# TLV75533PDRVR.net
KiCad netlist of a schematic drawn in Altium Designer
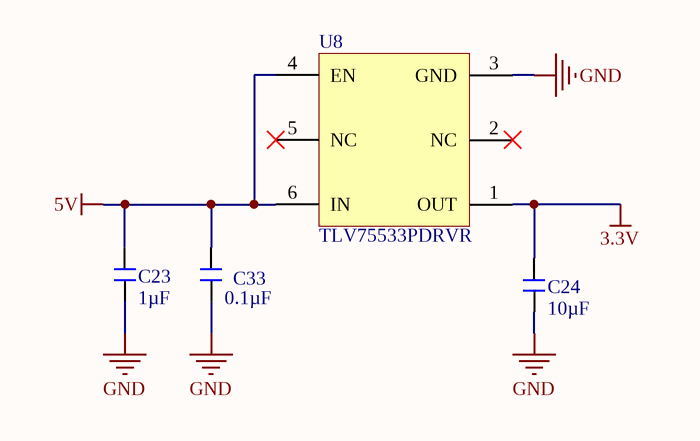
[diagram p0: TLV75533PDRVR.SchDoc]

(export (version "E")
  (design (tool "Eeschema 10.0.6"))
  (components
    (comp (ref "C23")
      (value "1µF")
      (footprint "402 capacitor - duplicate")
      (description "CAP SMD 402")
      (fields (field (name "MPN") "GRM155R6YA105KE11D") (field (name "Comment") "0402 capacitor"))
      (libsource (lib "Schlib1") (part "CAP SMD 402"))
    )
    (comp (ref "C24")
      (value "10µF")
      (footprint "603 CAPACITOR")
      (description "CON SMD 0603")
      (fields (field (name "MPN") "GRM188R61E106MA73D") (field (name "Comment") "0603 CAPACİTOR"))
      (libsource (lib "Schlib1") (part "CON SMD 0603"))
    )
    (comp (ref "C33")
      (value "0.1µF")
      (footprint "402 capacitor - duplicate")
      (description "CAP SMD 402")
      (fields (field (name "MPN") "CL05A104KA5NNNC") (field (name "Comment") "0402 capacitor"))
      (libsource (lib "Schlib1") (part "CAP SMD 402"))
    )
    (comp (ref "U8")
      (value "TLV75533PDRVR")
      (footprint "TLV75533PDRVR")
      (description "IC REG LINEAR 3.3V 500MA 6-WSON")
      (libsource (lib "Schlib1") (part "TLV75533PDRVR"))
    )
  )
  (nets
    (net (code "1") (name "3.3V") (class "Default")
      (node (ref "C24") (pin "2") (pintype "passive"))
      (node (ref "U8") (pin "1") (pinfunction "OUT_1") (pintype "passive"))
    )
    (net (code "2") (name "5V") (class "Default")
      (node (ref "C23") (pin "2") (pintype "passive"))
      (node (ref "C33") (pin "2") (pintype "passive"))
      (node (ref "U8") (pin "4") (pinfunction "EN_4") (pintype "passive"))
      (node (ref "U8") (pin "6") (pinfunction "IN_6") (pintype "passive"))
    )
    (net (code "3") (name "GND") (class "Default")
      (node (ref "C23") (pin "1") (pintype "passive"))
      (node (ref "C24") (pin "1") (pintype "passive"))
      (node (ref "C33") (pin "1") (pintype "passive"))
      (node (ref "U8") (pin "3") (pinfunction "GND_3") (pintype "passive"))
    )
    (net (code "4") (name "unconnected-(U8-NC-Pad2)") (class "Default")
      (node (ref "U8") (pin "2") (pinfunction "NC_2") (pintype "passive+no_connect"))
    )
    (net (code "5") (name "unconnected-(U8-NC-Pad5)") (class "Default")
      (node (ref "U8") (pin "5") (pinfunction "NC_5") (pintype "passive+no_connect"))
    )
  )
)
